# MotherBoard.net
KiCad netlist of a schematic drawn in Altium Designer
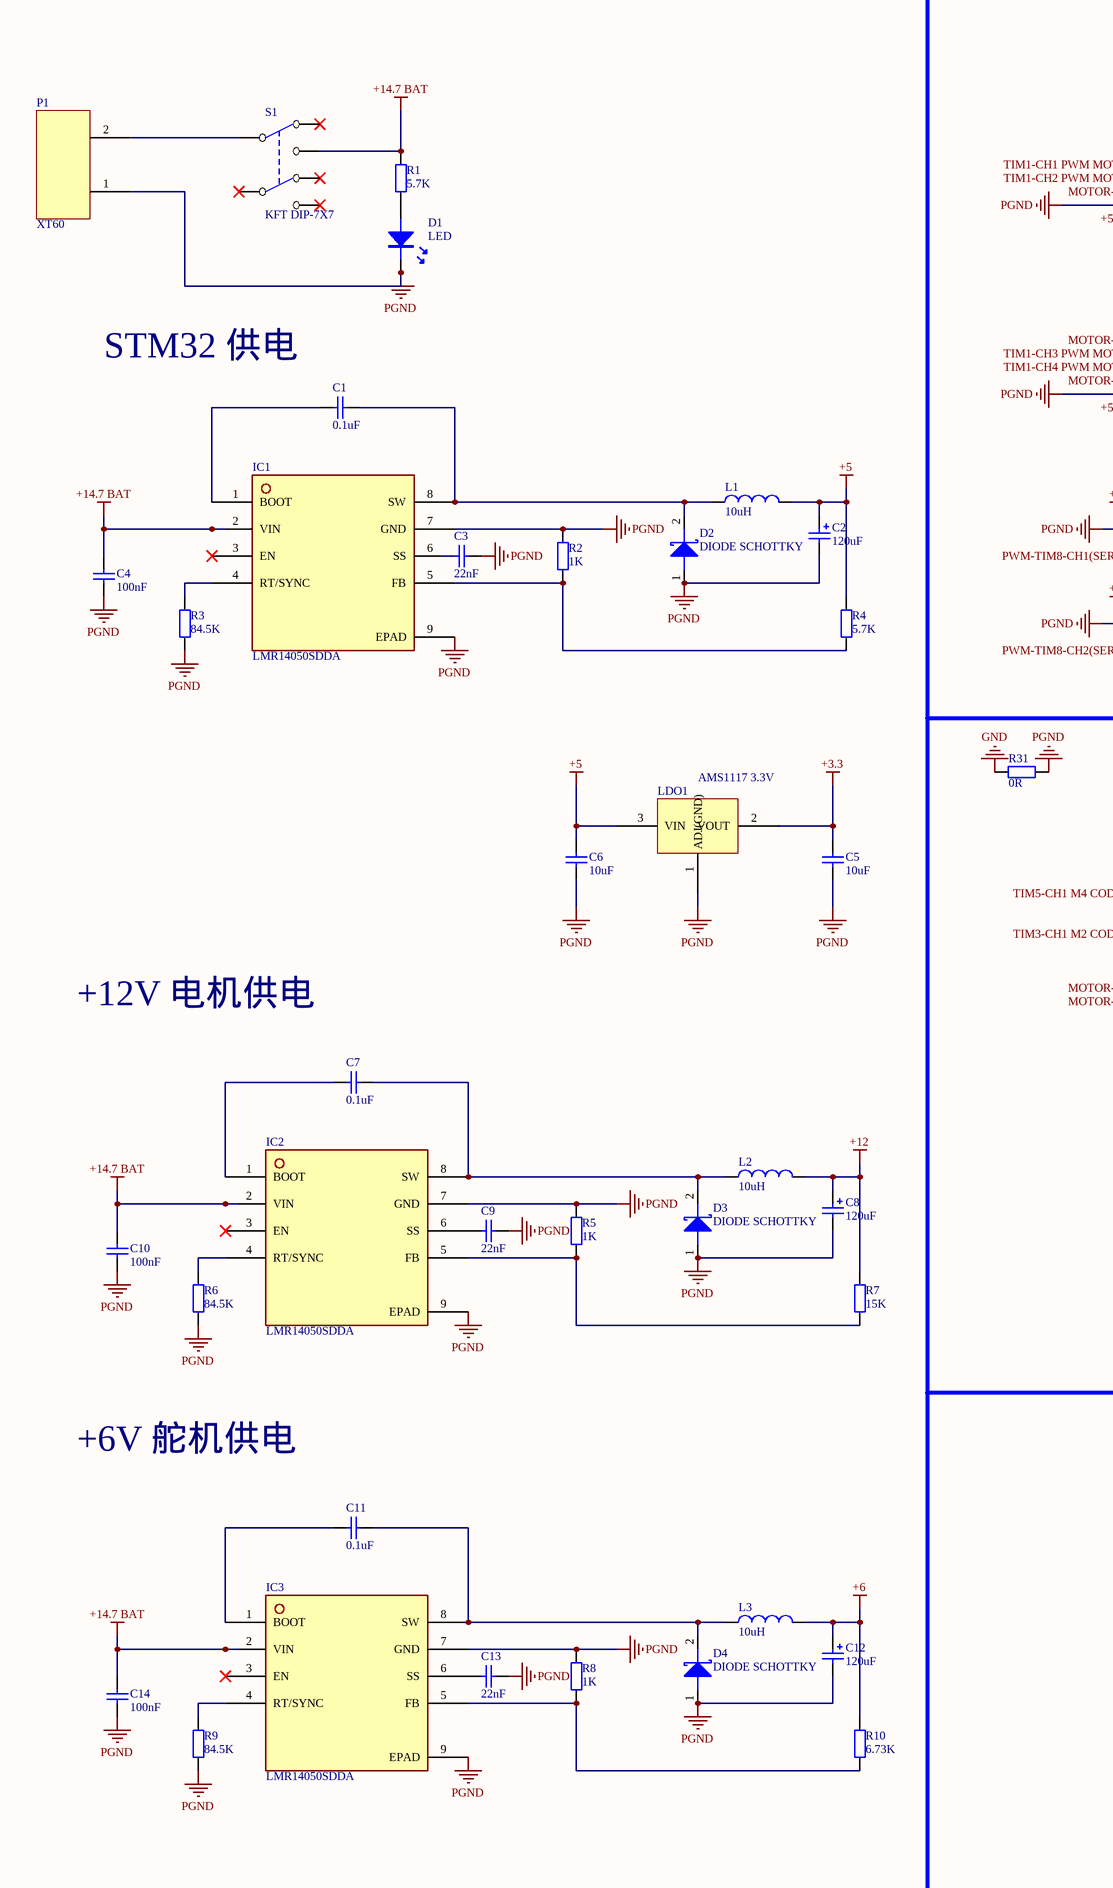
[diagram p0: MotherBoard.SchDoc, left]
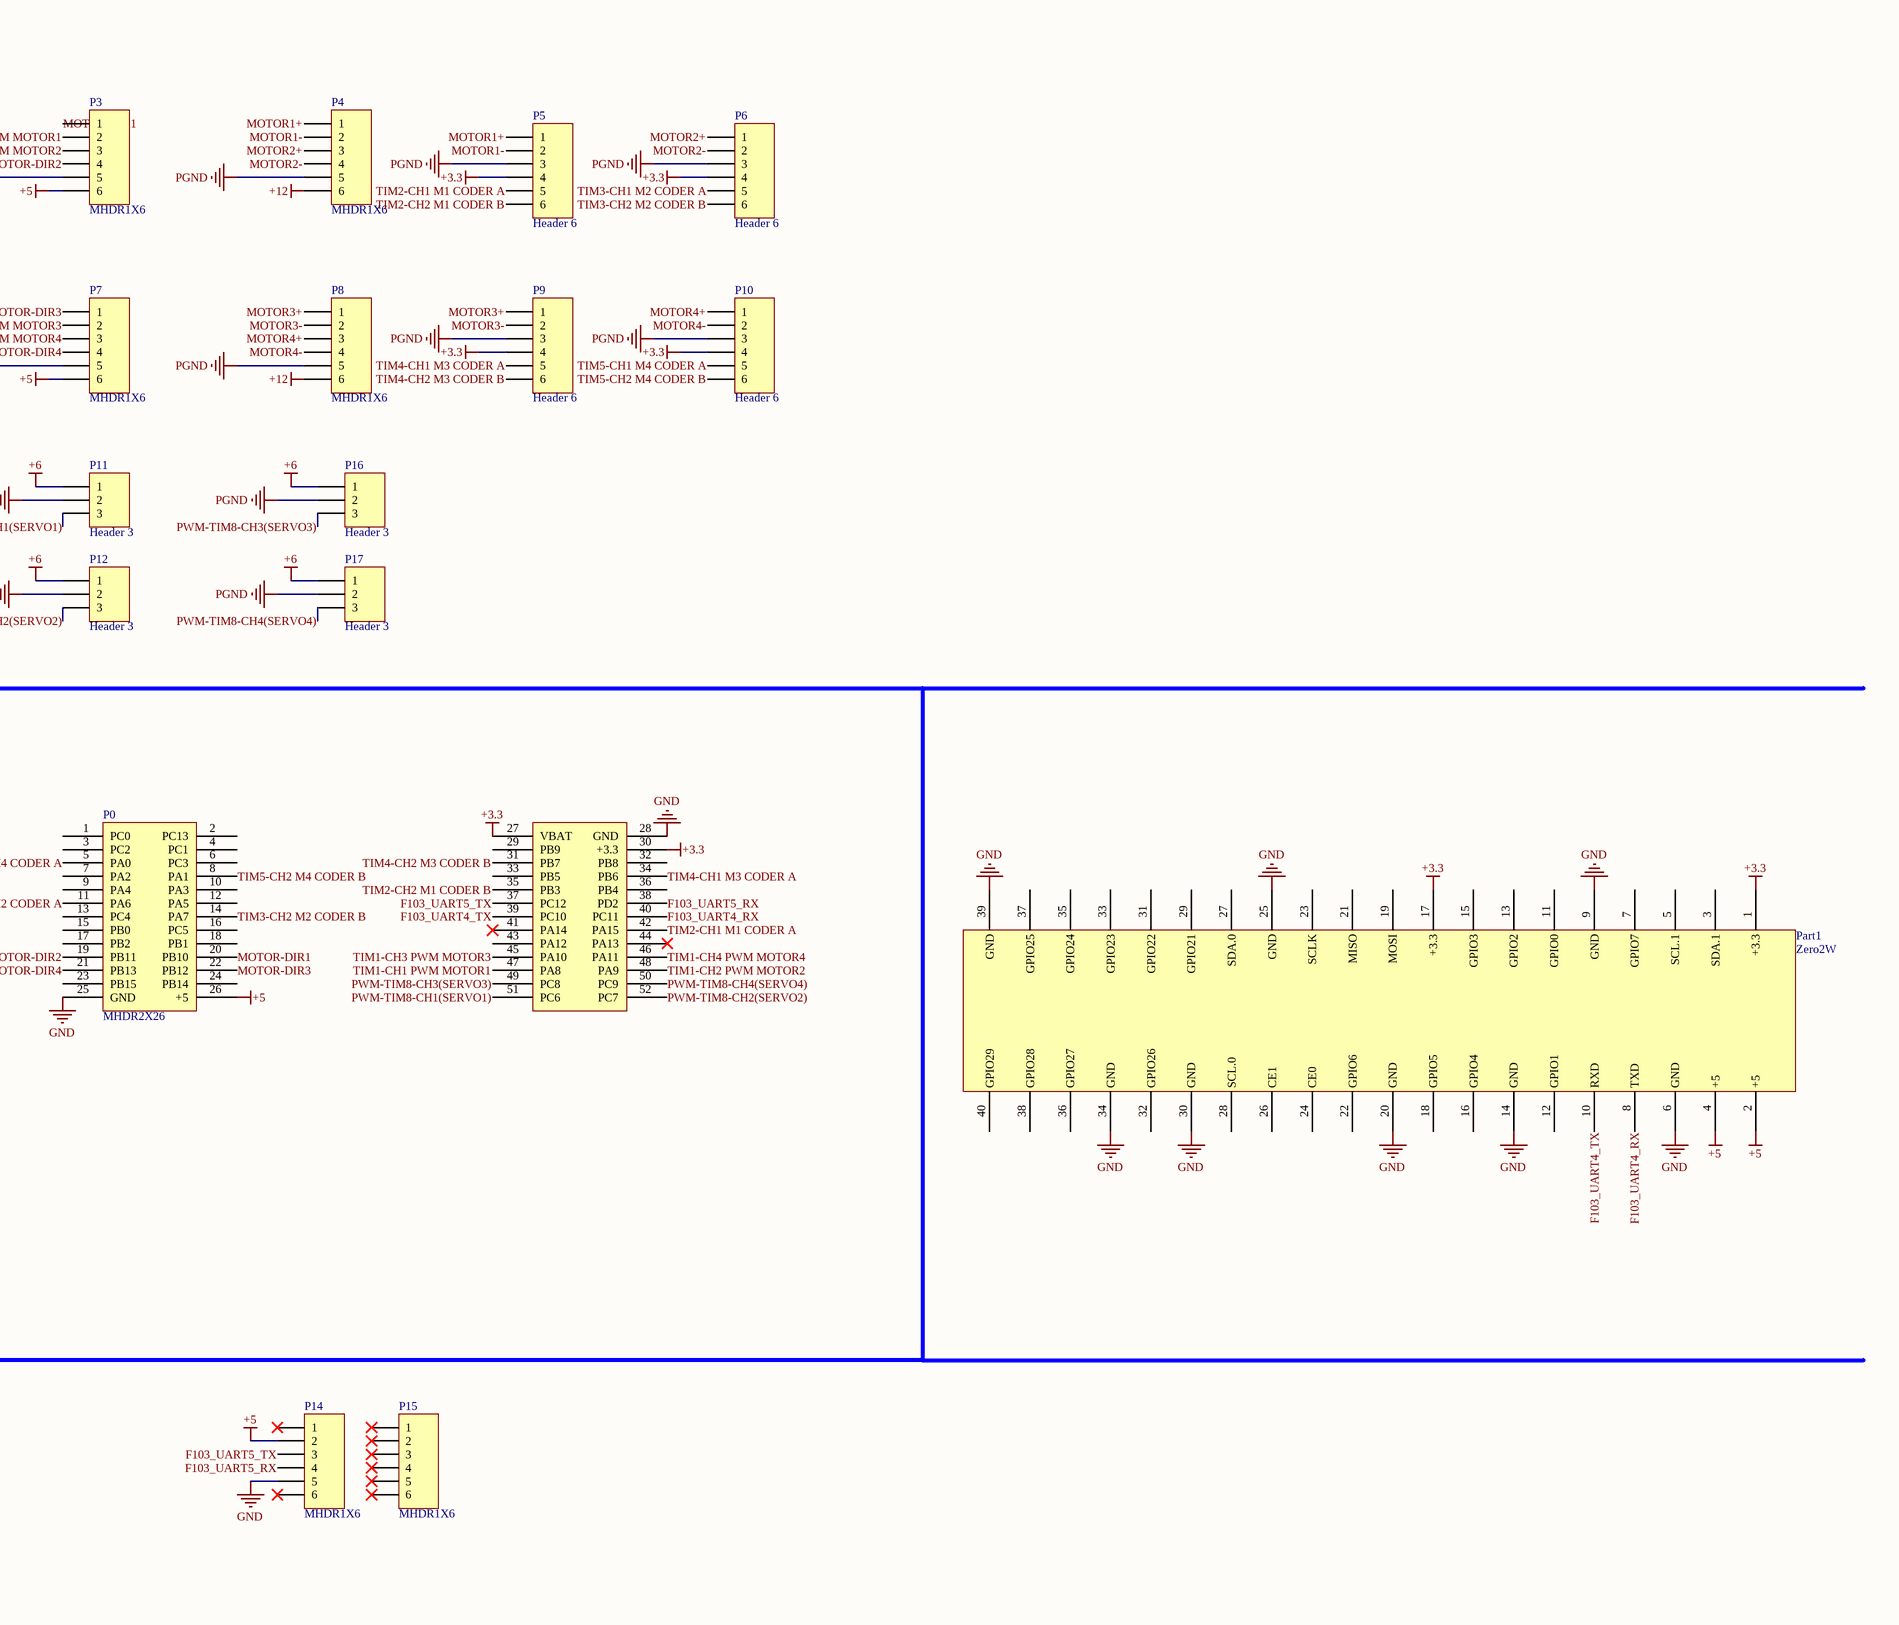
[diagram p1: MotherBoard.SchDoc, right]

(export (version "E")
  (design (tool "Eeschema 10.0.6"))
  (components
    (comp (ref "C1")
      (value "0.1uF")
      (footprint "CAPC2012X10M")
      (description "Capacitor 0.1uF")
      (fields (field (name "PUBLISHER") "Altium Limited"))
      (libsource (lib "Lib1") (part "Cap"))
    )
    (comp (ref "C2")
      (value "120uF")
      (footprint "CAP 6.3x15")
      (description "Polarized Capacitor (Radial)")
      (fields (field (name "PUBLISHER") "Altium Limited"))
      (libsource (lib "Lib1") (part "Cap Pol"))
    )
    (comp (ref "C3")
      (value "22nF")
      (footprint "CAPC2012X10M")
      (description "Capacitor")
      (fields (field (name "PUBLISHER") "Altium Limited"))
      (libsource (lib "Lib1") (part "Cap"))
    )
    (comp (ref "C4")
      (value "100nF")
      (footprint "CAPC2012X10M")
      (description "Capacitor")
      (fields (field (name "PUBLISHER") "Altium Limited"))
      (libsource (lib "Lib1") (part "Cap"))
    )
    (comp (ref "C5")
      (value "10uF")
      (footprint "CAPC2012X10M")
      (description "Capacitor")
      (fields (field (name "PUBLISHER") "Altium Limited"))
      (libsource (lib "Lib1") (part "Cap"))
    )
    (comp (ref "C6")
      (value "10uF")
      (footprint "CAPC2012X10M")
      (description "Capacitor")
      (fields (field (name "PUBLISHER") "Altium Limited"))
      (libsource (lib "Lib1") (part "Cap"))
    )
    (comp (ref "C7")
      (value "0.1uF")
      (footprint "CAPC2012X10M")
      (description "Capacitor")
      (fields (field (name "PUBLISHER") "Altium Limited"))
      (libsource (lib "Lib1") (part "Cap"))
    )
    (comp (ref "C8")
      (value "120uF")
      (footprint "CAP 6.3x15")
      (description "Polarized Capacitor (Radial)")
      (fields (field (name "PUBLISHER") "Altium Limited"))
      (libsource (lib "Lib1") (part "Cap Pol"))
    )
    (comp (ref "C9")
      (value "22nF")
      (footprint "CAPC2012X10M")
      (description "Capacitor")
      (fields (field (name "PUBLISHER") "Altium Limited"))
      (libsource (lib "Lib1") (part "Cap"))
    )
    (comp (ref "C10")
      (value "100nF")
      (footprint "CAPC2012X10M")
      (description "Capacitor")
      (fields (field (name "PUBLISHER") "Altium Limited"))
      (libsource (lib "Lib1") (part "Cap"))
    )
    (comp (ref "C11")
      (value "0.1uF")
      (footprint "CAPC2012X10M")
      (description "Capacitor")
      (fields (field (name "PUBLISHER") "Altium Limited"))
      (libsource (lib "Lib1") (part "Cap"))
    )
    (comp (ref "C12")
      (value "120uF")
      (footprint "CAP 6.3x15")
      (description "Polarized Capacitor (Radial)")
      (fields (field (name "PUBLISHER") "Altium Limited"))
      (libsource (lib "Lib1") (part "Cap Pol"))
    )
    (comp (ref "C13")
      (value "22nF")
      (footprint "CAPC2012X10M")
      (description "Capacitor")
      (fields (field (name "PUBLISHER") "Altium Limited"))
      (libsource (lib "Lib1") (part "Cap"))
    )
    (comp (ref "C14")
      (value "100nF")
      (footprint "CAPC2012X10M")
      (description "Capacitor")
      (fields (field (name "PUBLISHER") "Altium Limited"))
      (libsource (lib "Lib1") (part "Cap"))
    )
    (comp (ref "D1") (value "LED") (footprint "LED-0805") (libsource (lib "Lib1") (part "LED")))
    (comp (ref "D2")
      (value "DIODE SCHOTTKY")
      (footprint "SMA")
      (description "肖特基二极管")
      (libsource (lib "Lib1") (part "DIODE SCHOTTKY"))
    )
    (comp (ref "D3")
      (value "DIODE SCHOTTKY")
      (footprint "SMA")
      (description "肖特基二极管")
      (libsource (lib "Lib1") (part "DIODE SCHOTTKY"))
    )
    (comp (ref "D4")
      (value "DIODE SCHOTTKY")
      (footprint "SMA")
      (description "肖特基二极管")
      (libsource (lib "Lib1") (part "DIODE SCHOTTKY"))
    )
    (comp (ref "IC1")
      (value "LMR14050SDDA")
      (footprint "SOP127P600X170_HS-9M")
      (libsource (lib "Schlib1") (part "LMR14050SDDA"))
    )
    (comp (ref "IC2")
      (value "LMR14050SDDA")
      (footprint "SOP127P600X170_HS-9M")
      (libsource (lib "Schlib1") (part "LMR14050SDDA"))
    )
    (comp (ref "IC3")
      (value "LMR14050SDDA")
      (footprint "SOP127P600X170_HS-9M")
      (libsource (lib "Schlib1") (part "LMR14050SDDA"))
    )
    (comp (ref "L1")
      (value "10uH")
      (footprint "INDP4442X20M")
      (description "Inductor")
      (fields (field (name "PUBLISHER") "Altium Limited"))
      (libsource (lib "Lib1") (part "Inductor"))
    )
    (comp (ref "L2")
      (value "10uH")
      (footprint "INDP4442X20M")
      (description "Inductor")
      (fields (field (name "PUBLISHER") "Altium Limited"))
      (libsource (lib "Lib1") (part "Inductor"))
    )
    (comp (ref "L3")
      (value "10uH")
      (footprint "INDP4442X20M")
      (description "Inductor")
      (fields (field (name "PUBLISHER") "Altium Limited"))
      (libsource (lib "Lib1") (part "Inductor"))
    )
    (comp (ref "LDO1")
      (value "AMS1117 3.3V")
      (footprint "SOT230P700X180-4M")
      (libsource (lib "Lib1") (part "AMS1117 3.3V"))
    )
    (comp (ref "P0")
      (value "MHDR2X26")
      (footprint "PCBComponent_1")
      (description "Header, 52-Pin, Dual row")
      (fields (field (name "PUBLISHER") "Altium Limited"))
      (libsource (lib "STM32F103RCT6核心板--接口原理图库") (part "MHDR2X26"))
    )
    (comp (ref "P1") (value "XT60") (footprint "XT60H-F") (libsource (lib "Lib1") (part "XT60")))
    (comp (ref "P3")
      (value "MHDR1X6")
      (footprint "MPIN-6-2.54-1.0")
      (description "Header, 6-Pin")
      (fields (field (name "PUBLISHER") "Altium Limited"))
      (libsource (lib "Miscellaneous Connectors") (part "MHDR1X6"))
    )
    (comp (ref "P4")
      (value "MHDR1X6")
      (footprint "MPIN-6-2.54-1.0")
      (description "Header, 6-Pin")
      (fields (field (name "PUBLISHER") "Altium Limited"))
      (libsource (lib "Miscellaneous Connectors") (part "MHDR1X6"))
    )
    (comp (ref "P5")
      (value "Header 6")
      (footprint "HDR1X6")
      (description "Header, 6-Pin")
      (fields (field (name "PUBLISHER") "Altium Limited"))
      (libsource (lib "Miscellaneous Connectors") (part "Header 6"))
    )
    (comp (ref "P6")
      (value "Header 6")
      (footprint "HDR1X6")
      (description "Header, 6-Pin")
      (fields (field (name "PUBLISHER") "Altium Limited"))
      (libsource (lib "Miscellaneous Connectors") (part "Header 6"))
    )
    (comp (ref "P7")
      (value "MHDR1X6")
      (footprint "MPIN-6-2.54-1.0")
      (description "Header, 6-Pin")
      (fields (field (name "PUBLISHER") "Altium Limited"))
      (libsource (lib "Miscellaneous Connectors") (part "MHDR1X6"))
    )
    (comp (ref "P8")
      (value "MHDR1X6")
      (footprint "MPIN-6-2.54-1.0")
      (description "Header, 6-Pin")
      (fields (field (name "PUBLISHER") "Altium Limited"))
      (libsource (lib "Miscellaneous Connectors") (part "MHDR1X6"))
    )
    (comp (ref "P9")
      (value "Header 6")
      (footprint "HDR1X6")
      (description "Header, 6-Pin")
      (fields (field (name "PUBLISHER") "Altium Limited"))
      (libsource (lib "Miscellaneous Connectors") (part "Header 6"))
    )
    (comp (ref "P10")
      (value "Header 6")
      (footprint "HDR1X6")
      (description "Header, 6-Pin")
      (fields (field (name "PUBLISHER") "Altium Limited"))
      (libsource (lib "Miscellaneous Connectors") (part "Header 6"))
    )
    (comp (ref "P11")
      (value "Header 3")
      (footprint "HDR1X3")
      (description "Header, 3-Pin")
      (fields (field (name "PUBLISHER") "Altium Limited"))
      (libsource (lib "Miscellaneous Connectors") (part "Header 3"))
    )
    (comp (ref "P12")
      (value "Header 3")
      (footprint "HDR1X3")
      (description "Header, 3-Pin")
      (fields (field (name "PUBLISHER") "Altium Limited"))
      (libsource (lib "Miscellaneous Connectors") (part "Header 3"))
    )
    (comp (ref "P14")
      (value "MHDR1X6")
      (footprint "MPIN-6-2.54-1.0")
      (description "Header, 6-Pin")
      (fields (field (name "PUBLISHER") "Altium Limited"))
      (libsource (lib "Miscellaneous Connectors") (part "MHDR1X6"))
    )
    (comp (ref "P15")
      (value "MHDR1X6")
      (footprint "MPIN-6-2.54-1.0")
      (description "Header, 6-Pin")
      (fields (field (name "PUBLISHER") "Altium Limited"))
      (libsource (lib "Miscellaneous Connectors") (part "MHDR1X6"))
    )
    (comp (ref "P16")
      (value "Header 3")
      (footprint "HDR1X3")
      (description "Header, 3-Pin")
      (fields (field (name "PUBLISHER") "Altium Limited"))
      (libsource (lib "Miscellaneous Connectors") (part "Header 3"))
    )
    (comp (ref "P17")
      (value "Header 3")
      (footprint "HDR1X3")
      (description "Header, 3-Pin")
      (fields (field (name "PUBLISHER") "Altium Limited"))
      (libsource (lib "Miscellaneous Connectors") (part "Header 3"))
    )
    (comp (ref "Part1") (value "Zero2W") (footprint "Zero2W") (libsource (lib "Zero2W") (part "Zero2W")))
    (comp (ref "R1")
      (value "5.7K")
      (footprint "0805")
      (description "Resistor")
      (fields (field (name "PUBLISHER") "Altium Limited"))
      (libsource (lib "Lib1") (part "Res"))
    )
    (comp (ref "R2")
      (value "1K")
      (footprint "0805")
      (description "Resistor")
      (fields (field (name "PUBLISHER") "Altium Limited"))
      (libsource (lib "Lib1") (part "Res"))
    )
    (comp (ref "R3")
      (value "84.5K")
      (footprint "0805")
      (description "Resistor")
      (fields (field (name "PUBLISHER") "Altium Limited"))
      (libsource (lib "Lib1") (part "Res"))
    )
    (comp (ref "R4")
      (value "5.7K")
      (footprint "0805")
      (description "Resistor")
      (fields (field (name "PUBLISHER") "Altium Limited"))
      (libsource (lib "Lib1") (part "Res"))
    )
    (comp (ref "R5")
      (value "1K")
      (footprint "0805")
      (description "Resistor")
      (fields (field (name "PUBLISHER") "Altium Limited"))
      (libsource (lib "Lib1") (part "Res"))
    )
    (comp (ref "R6")
      (value "84.5K")
      (footprint "0805")
      (description "Resistor")
      (fields (field (name "PUBLISHER") "Altium Limited"))
      (libsource (lib "Lib1") (part "Res"))
    )
    (comp (ref "R7")
      (value "15K")
      (footprint "0805")
      (description "Resistor")
      (fields (field (name "PUBLISHER") "Altium Limited"))
      (libsource (lib "Lib1") (part "Res"))
    )
    (comp (ref "R8")
      (value "1K")
      (footprint "0805")
      (description "Resistor")
      (fields (field (name "PUBLISHER") "Altium Limited"))
      (libsource (lib "Lib1") (part "Res"))
    )
    (comp (ref "R9")
      (value "84.5K")
      (footprint "0805")
      (description "Resistor")
      (fields (field (name "PUBLISHER") "Altium Limited"))
      (libsource (lib "Lib1") (part "Res"))
    )
    (comp (ref "R10")
      (value "6.73K")
      (footprint "0805")
      (description "Resistor")
      (fields (field (name "PUBLISHER") "Altium Limited"))
      (libsource (lib "Lib1") (part "Res"))
    )
    (comp (ref "R31")
      (value "0R")
      (footprint "0805")
      (description "Resistor")
      (fields (field (name "PUBLISHER") "Altium Limited"))
      (libsource (lib "") (part "Res_1"))
    )
    (comp (ref "S1")
      (value "KFT DIP-7X7")
      (footprint "7X7 DIP")
      (libsource (lib "Lib1") (part "KFT DIP-7X7"))
    )
  )
  (nets
    (net (code "1") (name "+3.3") (class "Default")
      (node (ref "C5") (pin "2") (pinfunction "2_2") (pintype "passive"))
      (node (ref "LDO1") (pin "2") (pinfunction "VOUT_2") (pintype "passive"))
      (node (ref "P0") (pin "27") (pinfunction "VBAT_27") (pintype "passive"))
      (node (ref "P0") (pin "30") (pinfunction "+3.3_30") (pintype "passive"))
      (node (ref "P10") (pin "4") (pinfunction "4_4") (pintype "passive"))
      (node (ref "P5") (pin "4") (pinfunction "4_4") (pintype "passive"))
      (node (ref "P6") (pin "4") (pinfunction "4_4") (pintype "passive"))
      (node (ref "P9") (pin "4") (pinfunction "4_4") (pintype "passive"))
      (node (ref "Part1") (pin "1") (pinfunction "+3.3_1") (pintype "passive"))
      (node (ref "Part1") (pin "17") (pinfunction "+3.3_17") (pintype "passive"))
    )
    (net (code "2") (name "+5") (class "Default")
      (node (ref "C2") (pin "1") (pinfunction "1_1") (pintype "passive"))
      (node (ref "C6") (pin "2") (pinfunction "2_2") (pintype "passive"))
      (node (ref "L1") (pin "2") (pinfunction "2_2") (pintype "passive"))
      (node (ref "LDO1") (pin "3") (pinfunction "VIN_3") (pintype "passive"))
      (node (ref "P0") (pin "26") (pinfunction "+5_26") (pintype "passive"))
      (node (ref "P14") (pin "2") (pinfunction "2_2") (pintype "passive"))
      (node (ref "P3") (pin "6") (pinfunction "6_6") (pintype "passive"))
      (node (ref "P7") (pin "6") (pinfunction "6_6") (pintype "passive"))
      (node (ref "Part1") (pin "2") (pinfunction "+5_2") (pintype "passive"))
      (node (ref "Part1") (pin "4") (pinfunction "+5_4") (pintype "passive"))
      (node (ref "R4") (pin "2") (pinfunction "2_2") (pintype "passive"))
    )
    (net (code "3") (name "+6") (class "Default")
      (node (ref "C12") (pin "1") (pinfunction "1_1") (pintype "passive"))
      (node (ref "L3") (pin "2") (pinfunction "2_2") (pintype "passive"))
      (node (ref "P11") (pin "1") (pinfunction "1_1") (pintype "passive"))
      (node (ref "P12") (pin "1") (pinfunction "1_1") (pintype "passive"))
      (node (ref "P16") (pin "1") (pinfunction "1_1") (pintype "passive"))
      (node (ref "P17") (pin "1") (pinfunction "1_1") (pintype "passive"))
      (node (ref "R10") (pin "2") (pinfunction "2_2") (pintype "passive"))
    )
    (net (code "4") (name "+12") (class "Default")
      (node (ref "C8") (pin "1") (pinfunction "1_1") (pintype "passive"))
      (node (ref "L2") (pin "2") (pinfunction "2_2") (pintype "passive"))
      (node (ref "P4") (pin "6") (pinfunction "6_6") (pintype "passive"))
      (node (ref "P8") (pin "6") (pinfunction "6_6") (pintype "passive"))
      (node (ref "R7") (pin "2") (pinfunction "2_2") (pintype "passive"))
    )
    (net (code "5") (name "+14.7 BAT") (class "Default")
      (node (ref "C10") (pin "2") (pinfunction "2_2") (pintype "passive"))
      (node (ref "C14") (pin "2") (pinfunction "2_2") (pintype "passive"))
      (node (ref "C4") (pin "2") (pinfunction "2_2") (pintype "passive"))
      (node (ref "IC1") (pin "2") (pinfunction "VIN_2") (pintype "passive"))
      (node (ref "IC2") (pin "2") (pinfunction "VIN_2") (pintype "passive"))
      (node (ref "IC3") (pin "2") (pinfunction "VIN_2") (pintype "passive"))
      (node (ref "R1") (pin "2") (pinfunction "2_2") (pintype "passive"))
      (node (ref "S1") (pin "1") (pinfunction "1_1") (pintype "passive"))
    )
    (net (code "6") (name "/F103_UART4_RX") (class "Default")
      (node (ref "P0") (pin "40") (pinfunction "PC11_40") (pintype "passive"))
      (node (ref "Part1") (pin "8") (pinfunction "TXD_8") (pintype "passive"))
    )
    (net (code "7") (name "/F103_UART4_TX") (class "Default")
      (node (ref "P0") (pin "39") (pinfunction "PC10_39") (pintype "passive"))
      (node (ref "Part1") (pin "10") (pinfunction "RXD_10") (pintype "passive"))
    )
    (net (code "8") (name "/F103_UART5_RX") (class "Default")
      (node (ref "P0") (pin "38") (pinfunction "PD2_38") (pintype "passive"))
      (node (ref "P14") (pin "4") (pinfunction "4_4") (pintype "passive"))
    )
    (net (code "9") (name "/F103_UART5_TX") (class "Default")
      (node (ref "P0") (pin "37") (pinfunction "PC12_37") (pintype "passive"))
      (node (ref "P14") (pin "3") (pinfunction "3_3") (pintype "passive"))
    )
    (net (code "10") (name "/MOTOR-DIR1") (class "Default")
      (node (ref "P0") (pin "20") (pinfunction "PB10_20") (pintype "passive"))
      (node (ref "P3") (pin "1") (pinfunction "1_1") (pintype "passive"))
    )
    (net (code "11") (name "/MOTOR-DIR2") (class "Default")
      (node (ref "P0") (pin "19") (pinfunction "PB11_19") (pintype "passive"))
      (node (ref "P3") (pin "4") (pinfunction "4_4") (pintype "passive"))
    )
    (net (code "12") (name "/MOTOR-DIR3") (class "Default")
      (node (ref "P0") (pin "22") (pinfunction "PB12_22") (pintype "passive"))
      (node (ref "P7") (pin "1") (pinfunction "1_1") (pintype "passive"))
    )
    (net (code "13") (name "/MOTOR-DIR4") (class "Default")
      (node (ref "P0") (pin "21") (pinfunction "PB13_21") (pintype "passive"))
      (node (ref "P7") (pin "4") (pinfunction "4_4") (pintype "passive"))
    )
    (net (code "14") (name "/MOTOR1+") (class "Default")
      (node (ref "P4") (pin "1") (pinfunction "1_1") (pintype "passive"))
      (node (ref "P5") (pin "1") (pinfunction "1_1") (pintype "passive"))
    )
    (net (code "15") (name "/MOTOR1-") (class "Default")
      (node (ref "P4") (pin "2") (pinfunction "2_2") (pintype "passive"))
      (node (ref "P5") (pin "2") (pinfunction "2_2") (pintype "passive"))
    )
    (net (code "16") (name "/MOTOR2+") (class "Default")
      (node (ref "P4") (pin "3") (pinfunction "3_3") (pintype "passive"))
      (node (ref "P6") (pin "1") (pinfunction "1_1") (pintype "passive"))
    )
    (net (code "17") (name "/MOTOR2-") (class "Default")
      (node (ref "P4") (pin "4") (pinfunction "4_4") (pintype "passive"))
      (node (ref "P6") (pin "2") (pinfunction "2_2") (pintype "passive"))
    )
    (net (code "18") (name "/MOTOR3+") (class "Default")
      (node (ref "P8") (pin "1") (pinfunction "1_1") (pintype "passive"))
      (node (ref "P9") (pin "1") (pinfunction "1_1") (pintype "passive"))
    )
    (net (code "19") (name "/MOTOR3-") (class "Default")
      (node (ref "P8") (pin "2") (pinfunction "2_2") (pintype "passive"))
      (node (ref "P9") (pin "2") (pinfunction "2_2") (pintype "passive"))
    )
    (net (code "20") (name "/MOTOR4+") (class "Default")
      (node (ref "P10") (pin "1") (pinfunction "1_1") (pintype "passive"))
      (node (ref "P8") (pin "3") (pinfunction "3_3") (pintype "passive"))
    )
    (net (code "21") (name "/MOTOR4-") (class "Default")
      (node (ref "P10") (pin "2") (pinfunction "2_2") (pintype "passive"))
      (node (ref "P8") (pin "4") (pinfunction "4_4") (pintype "passive"))
    )
    (net (code "22") (name "/PWM-TIM8-CH1(SERVO1)") (class "Default")
      (node (ref "P0") (pin "51") (pinfunction "PC6_51") (pintype "passive"))
      (node (ref "P11") (pin "3") (pinfunction "3_3") (pintype "passive"))
    )
    (net (code "23") (name "/PWM-TIM8-CH2(SERVO2)") (class "Default")
      (node (ref "P0") (pin "52") (pinfunction "PC7_52") (pintype "passive"))
      (node (ref "P12") (pin "3") (pinfunction "3_3") (pintype "passive"))
    )
    (net (code "24") (name "/PWM-TIM8-CH3(SERVO3)") (class "Default")
      (node (ref "P0") (pin "49") (pinfunction "PC8_49") (pintype "passive"))
      (node (ref "P16") (pin "3") (pinfunction "3_3") (pintype "passive"))
    )
    (net (code "25") (name "/PWM-TIM8-CH4(SERVO4)") (class "Default")
      (node (ref "P0") (pin "50") (pinfunction "PC9_50") (pintype "passive"))
      (node (ref "P17") (pin "3") (pinfunction "3_3") (pintype "passive"))
    )
    (net (code "26") (name "/TIM1-CH1 PWM MOTOR1") (class "Default")
      (node (ref "P0") (pin "47") (pinfunction "PA8_47") (pintype "passive"))
      (node (ref "P3") (pin "2") (pinfunction "2_2") (pintype "passive"))
    )
    (net (code "27") (name "/TIM1-CH2 PWM MOTOR2") (class "Default")
      (node (ref "P0") (pin "48") (pinfunction "PA9_48") (pintype "passive"))
      (node (ref "P3") (pin "3") (pinfunction "3_3") (pintype "passive"))
    )
    (net (code "28") (name "/TIM1-CH3 PWM MOTOR3") (class "Default")
      (node (ref "P0") (pin "45") (pinfunction "PA10_45") (pintype "passive"))
      (node (ref "P7") (pin "2") (pinfunction "2_2") (pintype "passive"))
    )
    (net (code "29") (name "/TIM1-CH4 PWM MOTOR4") (class "Default")
      (node (ref "P0") (pin "46") (pinfunction "PA11_46") (pintype "passive"))
      (node (ref "P7") (pin "3") (pinfunction "3_3") (pintype "passive"))
    )
    (net (code "30") (name "/TIM2-CH1 M1 CODER A") (class "Default")
      (node (ref "P0") (pin "42") (pinfunction "PA15_42") (pintype "passive"))
      (node (ref "P5") (pin "5") (pinfunction "5_5") (pintype "passive"))
    )
    (net (code "31") (name "/TIM2-CH2 M1 CODER B") (class "Default")
      (node (ref "P0") (pin "35") (pinfunction "PB3_35") (pintype "passive"))
      (node (ref "P5") (pin "6") (pinfunction "6_6") (pintype "passive"))
    )
    (net (code "32") (name "/TIM3-CH1 M2 CODER A") (class "Default")
      (node (ref "P0") (pin "11") (pinfunction "PA6_11") (pintype "passive"))
      (node (ref "P6") (pin "5") (pinfunction "5_5") (pintype "passive"))
    )
    (net (code "33") (name "/TIM3-CH2 M2 CODER B") (class "Default")
      (node (ref "P0") (pin "14") (pinfunction "PA7_14") (pintype "passive"))
      (node (ref "P6") (pin "6") (pinfunction "6_6") (pintype "passive"))
    )
    (net (code "34") (name "/TIM4-CH1 M3 CODER A") (class "Default")
      (node (ref "P0") (pin "34") (pinfunction "PB6_34") (pintype "passive"))
      (node (ref "P9") (pin "5") (pinfunction "5_5") (pintype "passive"))
    )
    (net (code "35") (name "/TIM4-CH2 M3 CODER B") (class "Default")
      (node (ref "P0") (pin "31") (pinfunction "PB7_31") (pintype "passive"))
      (node (ref "P9") (pin "6") (pinfunction "6_6") (pintype "passive"))
    )
    (net (code "36") (name "/TIM5-CH1 M4 CODER A") (class "Default")
      (node (ref "P0") (pin "5") (pinfunction "PA0_5") (pintype "passive"))
      (node (ref "P10") (pin "5") (pinfunction "5_5") (pintype "passive"))
    )
    (net (code "37") (name "/TIM5-CH2 M4 CODER B") (class "Default")
      (node (ref "P0") (pin "8") (pinfunction "PA1_8") (pintype "passive"))
      (node (ref "P10") (pin "6") (pinfunction "6_6") (pintype "passive"))
    )
    (net (code "38") (name "GND") (class "Default")
      (node (ref "P0") (pin "25") (pinfunction "GND_25") (pintype "passive"))
      (node (ref "P0") (pin "28") (pinfunction "GND_28") (pintype "passive"))
      (node (ref "P14") (pin "5") (pinfunction "5_5") (pintype "passive"))
      (node (ref "Part1") (pin "14") (pinfunction "GND_14") (pintype "passive"))
      (node (ref "Part1") (pin "20") (pinfunction "GND_20") (pintype "passive"))
      (node (ref "Part1") (pin "25") (pinfunction "GND_25") (pintype "passive"))
      (node (ref "Part1") (pin "30") (pinfunction "GND_30") (pintype "passive"))
      (node (ref "Part1") (pin "34") (pinfunction "GND_34") (pintype "passive"))
      (node (ref "Part1") (pin "39") (pinfunction "GND_39") (pintype "passive"))
      (node (ref "Part1") (pin "6") (pinfunction "GND_6") (pintype "passive"))
      (node (ref "Part1") (pin "9") (pinfunction "GND_9") (pintype "passive"))
      (node (ref "R31") (pin "2") (pinfunction "2_2") (pintype "passive"))
    )
    (net (code "39") (name "Net-(D1-Pad1)") (class "Default")
      (node (ref "D1") (pin "1") (pinfunction "1_1") (pintype "passive"))
      (node (ref "R1") (pin "1") (pinfunction "1_1") (pintype "passive"))
    )
    (net (code "40") (name "Net-(IC1-BOOT)") (class "Default")
      (node (ref "C1") (pin "1") (pinfunction "1_1") (pintype "passive"))
      (node (ref "IC1") (pin "1") (pinfunction "BOOT_1") (pintype "passive"))
    )
    (net (code "41") (name "Net-(IC1-FB)") (class "Default")
      (node (ref "IC1") (pin "5") (pinfunction "FB_5") (pintype "passive"))
      (node (ref "R2") (pin "1") (pinfunction "1_1") (pintype "passive"))
      (node (ref "R4") (pin "1") (pinfunction "1_1") (pintype "passive"))
    )
    (net (code "42") (name "Net-(IC1-RT{slash}SYNC)") (class "Default")
      (node (ref "IC1") (pin "4") (pinfunction "RT/SYNC_4") (pintype "passive"))
      (node (ref "R3") (pin "2") (pinfunction "2_2") (pintype "passive"))
    )
    (net (code "43") (name "Net-(IC1-SS)") (class "Default")
      (node (ref "C3") (pin "1") (pinfunction "1_1") (pintype "passive"))
      (node (ref "IC1") (pin "6") (pinfunction "SS_6") (pintype "passive"))
    )
    (net (code "44") (name "Net-(IC1-SW)") (class "Default")
      (node (ref "C1") (pin "2") (pinfunction "2_2") (pintype "passive"))
      (node (ref "D2") (pin "2") (pinfunction "2_2") (pintype "passive"))
      (node (ref "IC1") (pin "8") (pinfunction "SW_8") (pintype "passive"))
      (node (ref "L1") (pin "1") (pinfunction "1_1") (pintype "passive"))
    )
    (net (code "45") (name "Net-(IC2-BOOT)") (class "Default")
      (node (ref "C7") (pin "1") (pinfunction "1_1") (pintype "passive"))
      (node (ref "IC2") (pin "1") (pinfunction "BOOT_1") (pintype "passive"))
    )
    (net (code "46") (name "Net-(IC2-FB)") (class "Default")
      (node (ref "IC2") (pin "5") (pinfunction "FB_5") (pintype "passive"))
      (node (ref "R5") (pin "1") (pinfunction "1_1") (pintype "passive"))
      (node (ref "R7") (pin "1") (pinfunction "1_1") (pintype "passive"))
    )
    (net (code "47") (name "Net-(IC2-RT{slash}SYNC)") (class "Default")
      (node (ref "IC2") (pin "4") (pinfunction "RT/SYNC_4") (pintype "passive"))
      (node (ref "R6") (pin "2") (pinfunction "2_2") (pintype "passive"))
    )
    (net (code "48") (name "Net-(IC2-SS)") (class "Default")
      (node (ref "C9") (pin "1") (pinfunction "1_1") (pintype "passive"))
      (node (ref "IC2") (pin "6") (pinfunction "SS_6") (pintype "passive"))
    )
    (net (code "49") (name "Net-(IC2-SW)") (class "Default")
      (node (ref "C7") (pin "2") (pinfunction "2_2") (pintype "passive"))
      (node (ref "D3") (pin "2") (pinfunction "2_2") (pintype "passive"))
      (node (ref "IC2") (pin "8") (pinfunction "SW_8") (pintype "passive"))
      (node (ref "L2") (pin "1") (pinfunction "1_1") (pintype "passive"))
    )
    (net (code "50") (name "Net-(IC3-BOOT)") (class "Default")
      (node (ref "C11") (pin "1") (pinfunction "1_1") (pintype "passive"))
      (node (ref "IC3") (pin "1") (pinfunction "BOOT_1") (pintype "passive"))
    )
    (net (code "51") (name "Net-(IC3-FB)") (class "Default")
      (node (ref "IC3") (pin "5") (pinfunction "FB_5") (pintype "passive"))
      (node (ref "R10") (pin "1") (pinfunction "1_1") (pintype "passive"))
      (node (ref "R8") (pin "1") (pinfunction "1_1") (pintype "passive"))
    )
    (net (code "52") (name "Net-(IC3-RT{slash}SYNC)") (class "Default")
      (node (ref "IC3") (pin "4") (pinfunction "RT/SYNC_4") (pintype "passive"))
      (node (ref "R9") (pin "2") (pinfunction "2_2") (pintype "passive"))
    )
    (net (code "53") (name "Net-(IC3-SS)") (class "Default")
      (node (ref "C13") (pin "1") (pinfunction "1_1") (pintype "passive"))
      (node (ref "IC3") (pin "6") (pinfunction "SS_6") (pintype "passive"))
    )
    (net (code "54") (name "Net-(IC3-SW)") (class "Default")
      (node (ref "C11") (pin "2") (pinfunction "2_2") (pintype "passive"))
      (node (ref "D4") (pin "2") (pinfunction "2_2") (pintype "passive"))
      (node (ref "IC3") (pin "8") (pinfunction "SW_8") (pintype "passive"))
      (node (ref "L3") (pin "1") (pinfunction "1_1") (pintype "passive"))
    )
    (net (code "55") (name "Net-(P1-Pad2)") (class "Default")
      (node (ref "P1") (pin "2") (pinfunction "2_2") (pintype "passive"))
      (node (ref "S1") (pin "2") (pinfunction "2_2") (pintype "passive"))
    )
    (net (code "56") (name "PGND") (class "Default")
      (node (ref "C10") (pin "1") (pinfunction "1_1") (pintype "passive"))
      (node (ref "C12") (pin "2") (pinfunction "2_2") (pintype "passive"))
      (node (ref "C13") (pin "2") (pinfunction "2_2") (pintype "passive"))
      (node (ref "C14") (pin "1") (pinfunction "1_1") (pintype "passive"))
      (node (ref "C2") (pin "2") (pinfunction "2_2") (pintype "passive"))
      (node (ref "C3") (pin "2") (pinfunction "2_2") (pintype "passive"))
      (node (ref "C4") (pin "1") (pinfunction "1_1") (pintype "passive"))
      (node (ref "C5") (pin "1") (pinfunction "1_1") (pintype "passive"))
      (node (ref "C6") (pin "1") (pinfunction "1_1") (pintype "passive"))
      (node (ref "C8") (pin "2") (pinfunction "2_2") (pintype "passive"))
      (node (ref "C9") (pin "2") (pinfunction "2_2") (pintype "passive"))
      (node (ref "D1") (pin "2") (pinfunction "2_2") (pintype "passive"))
      (node (ref "D2") (pin "1") (pinfunction "1_1") (pintype "passive"))
      (node (ref "D3") (pin "1") (pinfunction "1_1") (pintype "passive"))
      (node (ref "D4") (pin "1") (pinfunction "1_1") (pintype "passive"))
      (node (ref "IC1") (pin "7") (pinfunction "GND_7") (pintype "passive"))
      (node (ref "IC1") (pin "9") (pinfunction "EPAD_9") (pintype "passive"))
      (node (ref "IC2") (pin "7") (pinfunction "GND_7") (pintype "passive"))
      (node (ref "IC2") (pin "9") (pinfunction "EPAD_9") (pintype "passive"))
      (node (ref "IC3") (pin "7") (pinfunction "GND_7") (pintype "passive"))
      (node (ref "IC3") (pin "9") (pinfunction "EPAD_9") (pintype "passive"))
      (node (ref "LDO1") (pin "1") (pinfunction "ADJ(GND)_1") (pintype "passive"))
      (node (ref "P1") (pin "1") (pinfunction "1_1") (pintype "passive"))
      (node (ref "P10") (pin "3") (pinfunction "3_3") (pintype "passive"))
      (node (ref "P11") (pin "2") (pinfunction "2_2") (pintype "passive"))
      (node (ref "P12") (pin "2") (pinfunction "2_2") (pintype "passive"))
      (node (ref "P16") (pin "2") (pinfunction "2_2") (pintype "passive"))
      (node (ref "P17") (pin "2") (pinfunction "2_2") (pintype "passive"))
      (node (ref "P3") (pin "5") (pinfunction "5_5") (pintype "passive"))
      (node (ref "P4") (pin "5") (pinfunction "5_5") (pintype "passive"))
      (node (ref "P5") (pin "3") (pinfunction "3_3") (pintype "passive"))
      (node (ref "P6") (pin "3") (pinfunction "3_3") (pintype "passive"))
      (node (ref "P7") (pin "5") (pinfunction "5_5") (pintype "passive"))
      (node (ref "P8") (pin "5") (pinfunction "5_5") (pintype "passive"))
      (node (ref "P9") (pin "3") (pinfunction "3_3") (pintype "passive"))
      (node (ref "R2") (pin "2") (pinfunction "2_2") (pintype "passive"))
      (node (ref "R3") (pin "1") (pinfunction "1_1") (pintype "passive"))
      (node (ref "R31") (pin "1") (pinfunction "1_1") (pintype "passive"))
      (node (ref "R5") (pin "2") (pinfunction "2_2") (pintype "passive"))
      (node (ref "R6") (pin "1") (pinfunction "1_1") (pintype "passive"))
      (node (ref "R8") (pin "2") (pinfunction "2_2") (pintype "passive"))
      (node (ref "R9") (pin "1") (pinfunction "1_1") (pintype "passive"))
    )
    (net (code "57") (name "unconnected-(IC1-EN-Pad3)") (class "Default")
      (node (ref "IC1") (pin "3") (pinfunction "EN_3") (pintype "passive+no_connect"))
    )
    (net (code "58") (name "unconnected-(IC2-EN-Pad3)") (class "Default")
      (node (ref "IC2") (pin "3") (pinfunction "EN_3") (pintype "passive+no_connect"))
    )
    (net (code "59") (name "unconnected-(IC3-EN-Pad3)") (class "Default")
      (node (ref "IC3") (pin "3") (pinfunction "EN_3") (pintype "passive+no_connect"))
    )
    (net (code "60") (name "unconnected-(P0-PA2-Pad7)") (class "Default")
      (node (ref "P0") (pin "7") (pinfunction "PA2_7") (pintype "passive"))
    )
    (net (code "61") (name "unconnected-(P0-PA3-Pad10)") (class "Default")
      (node (ref "P0") (pin "10") (pinfunction "PA3_10") (pintype "passive"))
    )
    (net (code "62") (name "unconnected-(P0-PA4-Pad9)") (class "Default")
      (node (ref "P0") (pin "9") (pinfunction "PA4_9") (pintype "passive"))
    )
    (net (code "63") (name "unconnected-(P0-PA5-Pad12)") (class "Default")
      (node (ref "P0") (pin "12") (pinfunction "PA5_12") (pintype "passive"))
    )
    (net (code "64") (name "unconnected-(P0-PA12-Pad43)") (class "Default")
      (node (ref "P0") (pin "43") (pinfunction "PA12_43") (pintype "passive"))
    )
    (net (code "65") (name "unconnected-(P0-PA13-Pad44)") (class "Default")
      (node (ref "P0") (pin "44") (pinfunction "PA13_44") (pintype "passive+no_connect"))
    )
    (net (code "66") (name "unconnected-(P0-PA14-Pad41)") (class "Default")
      (node (ref "P0") (pin "41") (pinfunction "PA14_41") (pintype "passive+no_connect"))
    )
    (net (code "67") (name "unconnected-(P0-PB0-Pad15)") (class "Default")
      (node (ref "P0") (pin "15") (pinfunction "PB0_15") (pintype "passive"))
    )
    (net (code "68") (name "unconnected-(P0-PB1-Pad18)") (class "Default")
      (node (ref "P0") (pin "18") (pinfunction "PB1_18") (pintype "passive"))
    )
    (net (code "69") (name "unconnected-(P0-PB2-Pad17)") (class "Default")
      (node (ref "P0") (pin "17") (pinfunction "PB2_17") (pintype "passive"))
    )
    (net (code "70") (name "unconnected-(P0-PB4-Pad36)") (class "Default")
      (node (ref "P0") (pin "36") (pinfunction "PB4_36") (pintype "passive"))
    )
    (net (code "71") (name "unconnected-(P0-PB5-Pad33)") (class "Default")
      (node (ref "P0") (pin "33") (pinfunction "PB5_33") (pintype "passive"))
    )
    (net (code "72") (name "unconnected-(P0-PB8-Pad32)") (class "Default")
      (node (ref "P0") (pin "32") (pinfunction "PB8_32") (pintype "passive"))
    )
    (net (code "73") (name "unconnected-(P0-PB9-Pad29)") (class "Default")
      (node (ref "P0") (pin "29") (pinfunction "PB9_29") (pintype "passive"))
    )
    (net (code "74") (name "unconnected-(P0-PB14-Pad24)") (class "Default")
      (node (ref "P0") (pin "24") (pinfunction "PB14_24") (pintype "passive"))
    )
    (net (code "75") (name "unconnected-(P0-PB15-Pad23)") (class "Default")
      (node (ref "P0") (pin "23") (pinfunction "PB15_23") (pintype "passive"))
    )
    (net (code "76") (name "unconnected-(P0-PC0-Pad1)") (class "Default")
      (node (ref "P0") (pin "1") (pinfunction "PC0_1") (pintype "passive"))
    )
    (net (code "77") (name "unconnected-(P0-PC1-Pad4)") (class "Default")
      (node (ref "P0") (pin "4") (pinfunction "PC1_4") (pintype "passive"))
    )
    (net (code "78") (name "unconnected-(P0-PC2-Pad3)") (class "Default")
      (node (ref "P0") (pin "3") (pinfunction "PC2_3") (pintype "passive"))
    )
    (net (code "79") (name "unconnected-(P0-PC3-Pad6)") (class "Default")
      (node (ref "P0") (pin "6") (pinfunction "PC3_6") (pintype "passive"))
    )
    (net (code "80") (name "unconnected-(P0-PC4-Pad13)") (class "Default")
      (node (ref "P0") (pin "13") (pinfunction "PC4_13") (pintype "passive"))
    )
    (net (code "81") (name "unconnected-(P0-PC5-Pad16)") (class "Default")
      (node (ref "P0") (pin "16") (pinfunction "PC5_16") (pintype "passive"))
    )
    (net (code "82") (name "unconnected-(P0-PC13-Pad2)") (class "Default")
      (node (ref "P0") (pin "2") (pinfunction "PC13_2") (pintype "passive"))
    )
    (net (code "83") (name "unconnected-(P14-Pad1)") (class "Default")
      (node (ref "P14") (pin "1") (pinfunction "1_1") (pintype "passive+no_connect"))
    )
    (net (code "84") (name "unconnected-(P14-Pad6)") (class "Default")
      (node (ref "P14") (pin "6") (pinfunction "6_6") (pintype "passive+no_connect"))
    )
    (net (code "85") (name "unconnected-(P15-Pad1)") (class "Default")
      (node (ref "P15") (pin "1") (pinfunction "1_1") (pintype "passive+no_connect"))
    )
    (net (code "86") (name "unconnected-(P15-Pad2)") (class "Default")
      (node (ref "P15") (pin "2") (pinfunction "2_2") (pintype "passive+no_connect"))
    )
    (net (code "87") (name "unconnected-(P15-Pad3)") (class "Default")
      (node (ref "P15") (pin "3") (pinfunction "3_3") (pintype "passive+no_connect"))
    )
    (net (code "88") (name "unconnected-(P15-Pad4)") (class "Default")
      (node (ref "P15") (pin "4") (pinfunction "4_4") (pintype "passive+no_connect"))
    )
    (net (code "89") (name "unconnected-(P15-Pad5)") (class "Default")
      (node (ref "P15") (pin "5") (pinfunction "5_5") (pintype "passive+no_connect"))
    )
    (net (code "90") (name "unconnected-(P15-Pad6)") (class "Default")
      (node (ref "P15") (pin "6") (pinfunction "6_6") (pintype "passive+no_connect"))
    )
    (net (code "91") (name "unconnected-(Part1-CE0-Pad24)") (class "Default")
      (node (ref "Part1") (pin "24") (pinfunction "CE0_24") (pintype "passive"))
    )
    (net (code "92") (name "unconnected-(Part1-CE1-Pad26)") (class "Default")
      (node (ref "Part1") (pin "26") (pinfunction "CE1_26") (pintype "passive"))
    )
    (net (code "93") (name "unconnected-(Part1-GPIO0-Pad11)") (class "Default")
      (node (ref "Part1") (pin "11") (pinfunction "GPIO0_11") (pintype "passive"))
    )
    (net (code "94") (name "unconnected-(Part1-GPIO1-Pad12)") (class "Default")
      (node (ref "Part1") (pin "12") (pinfunction "GPIO1_12") (pintype "passive"))
    )
    (net (code "95") (name "unconnected-(Part1-GPIO2-Pad13)") (class "Default")
      (node (ref "Part1") (pin "13") (pinfunction "GPIO2_13") (pintype "passive"))
    )
    (net (code "96") (name "unconnected-(Part1-GPIO3-Pad15)") (class "Default")
      (node (ref "Part1") (pin "15") (pinfunction "GPIO3_15") (pintype "passive"))
    )
    (net (code "97") (name "unconnected-(Part1-GPIO4-Pad16)") (class "Default")
      (node (ref "Part1") (pin "16") (pinfunction "GPIO4_16") (pintype "passive"))
    )
    (net (code "98") (name "unconnected-(Part1-GPIO5-Pad18)") (class "Default")
      (node (ref "Part1") (pin "18") (pinfunction "GPIO5_18") (pintype "passive"))
    )
    (net (code "99") (name "unconnected-(Part1-GPIO6-Pad22)") (class "Default")
      (node (ref "Part1") (pin "22") (pinfunction "GPIO6_22") (pintype "passive"))
    )
    (net (code "100") (name "unconnected-(Part1-GPIO7-Pad7)") (class "Default")
      (node (ref "Part1") (pin "7") (pinfunction "GPIO7_7") (pintype "passive"))
    )
    (net (code "101") (name "unconnected-(Part1-GPIO21-Pad29)") (class "Default")
      (node (ref "Part1") (pin "29") (pinfunction "GPIO21_29") (pintype "passive"))
    )
    (net (code "102") (name "unconnected-(Part1-GPIO22-Pad31)") (class "Default")
      (node (ref "Part1") (pin "31") (pinfunction "GPIO22_31") (pintype "passive"))
    )
    (net (code "103") (name "unconnected-(Part1-GPIO23-Pad33)") (class "Default")
      (node (ref "Part1") (pin "33") (pinfunction "GPIO23_33") (pintype "passive"))
    )
    (net (code "104") (name "unconnected-(Part1-GPIO24-Pad35)") (class "Default")
      (node (ref "Part1") (pin "35") (pinfunction "GPIO24_35") (pintype "passive"))
    )
    (net (code "105") (name "unconnected-(Part1-GPIO25-Pad37)") (class "Default")
      (node (ref "Part1") (pin "37") (pinfunction "GPIO25_37") (pintype "passive"))
    )
    (net (code "106") (name "unconnected-(Part1-GPIO26-Pad32)") (class "Default")
      (node (ref "Part1") (pin "32") (pinfunction "GPIO26_32") (pintype "passive"))
    )
    (net (code "107") (name "unconnected-(Part1-GPIO27-Pad36)") (class "Default")
      (node (ref "Part1") (pin "36") (pinfunction "GPIO27_36") (pintype "passive"))
    )
    (net (code "108") (name "unconnected-(Part1-GPIO28-Pad38)") (class "Default")
      (node (ref "Part1") (pin "38") (pinfunction "GPIO28_38") (pintype "passive"))
    )
    (net (code "109") (name "unconnected-(Part1-GPIO29-Pad40)") (class "Default")
      (node (ref "Part1") (pin "40") (pinfunction "GPIO29_40") (pintype "passive"))
    )
    (net (code "110") (name "unconnected-(Part1-MISO-Pad21)") (class "Default")
      (node (ref "Part1") (pin "21") (pinfunction "MISO_21") (pintype "passive"))
    )
    (net (code "111") (name "unconnected-(Part1-MOSI-Pad19)") (class "Default")
      (node (ref "Part1") (pin "19") (pinfunction "MOSI_19") (pintype "passive"))
    )
    (net (code "112") (name "unconnected-(Part1-SCL.0-Pad28)") (class "Default")
      (node (ref "Part1") (pin "28") (pinfunction "SCL.0_28") (pintype "passive"))
    )
    (net (code "113") (name "unconnected-(Part1-SCL.1-Pad5)") (class "Default")
      (node (ref "Part1") (pin "5") (pinfunction "SCL.1_5") (pintype "passive"))
    )
    (net (code "114") (name "unconnected-(Part1-SCLK-Pad23)") (class "Default")
      (node (ref "Part1") (pin "23") (pinfunction "SCLK_23") (pintype "passive"))
    )
    (net (code "115") (name "unconnected-(Part1-SDA.0-Pad27)") (class "Default")
      (node (ref "Part1") (pin "27") (pinfunction "SDA.0_27") (pintype "passive"))
    )
    (net (code "116") (name "unconnected-(Part1-SDA.1-Pad3)") (class "Default")
      (node (ref "Part1") (pin "3") (pinfunction "SDA.1_3") (pintype "passive"))
    )
    (net (code "117") (name "unconnected-(S1-Pad3)") (class "Default")
      (node (ref "S1") (pin "3") (pinfunction "3_3") (pintype "passive+no_connect"))
    )
    (net (code "118") (name "unconnected-(S1-Pad4)") (class "Default")
      (node (ref "S1") (pin "4") (pinfunction "4_4") (pintype "passive+no_connect"))
    )
    (net (code "119") (name "unconnected-(S1-Pad5)") (class "Default")
      (node (ref "S1") (pin "5") (pinfunction "5_5") (pintype "passive+no_connect"))
    )
    (net (code "120") (name "unconnected-(S1-Pad6)") (class "Default")
      (node (ref "S1") (pin "6") (pinfunction "6_6") (pintype "passive+no_connect"))
    )
  )
)
